# usb-sys.net
KiCad netlist of a schematic drawn in Altium Designer
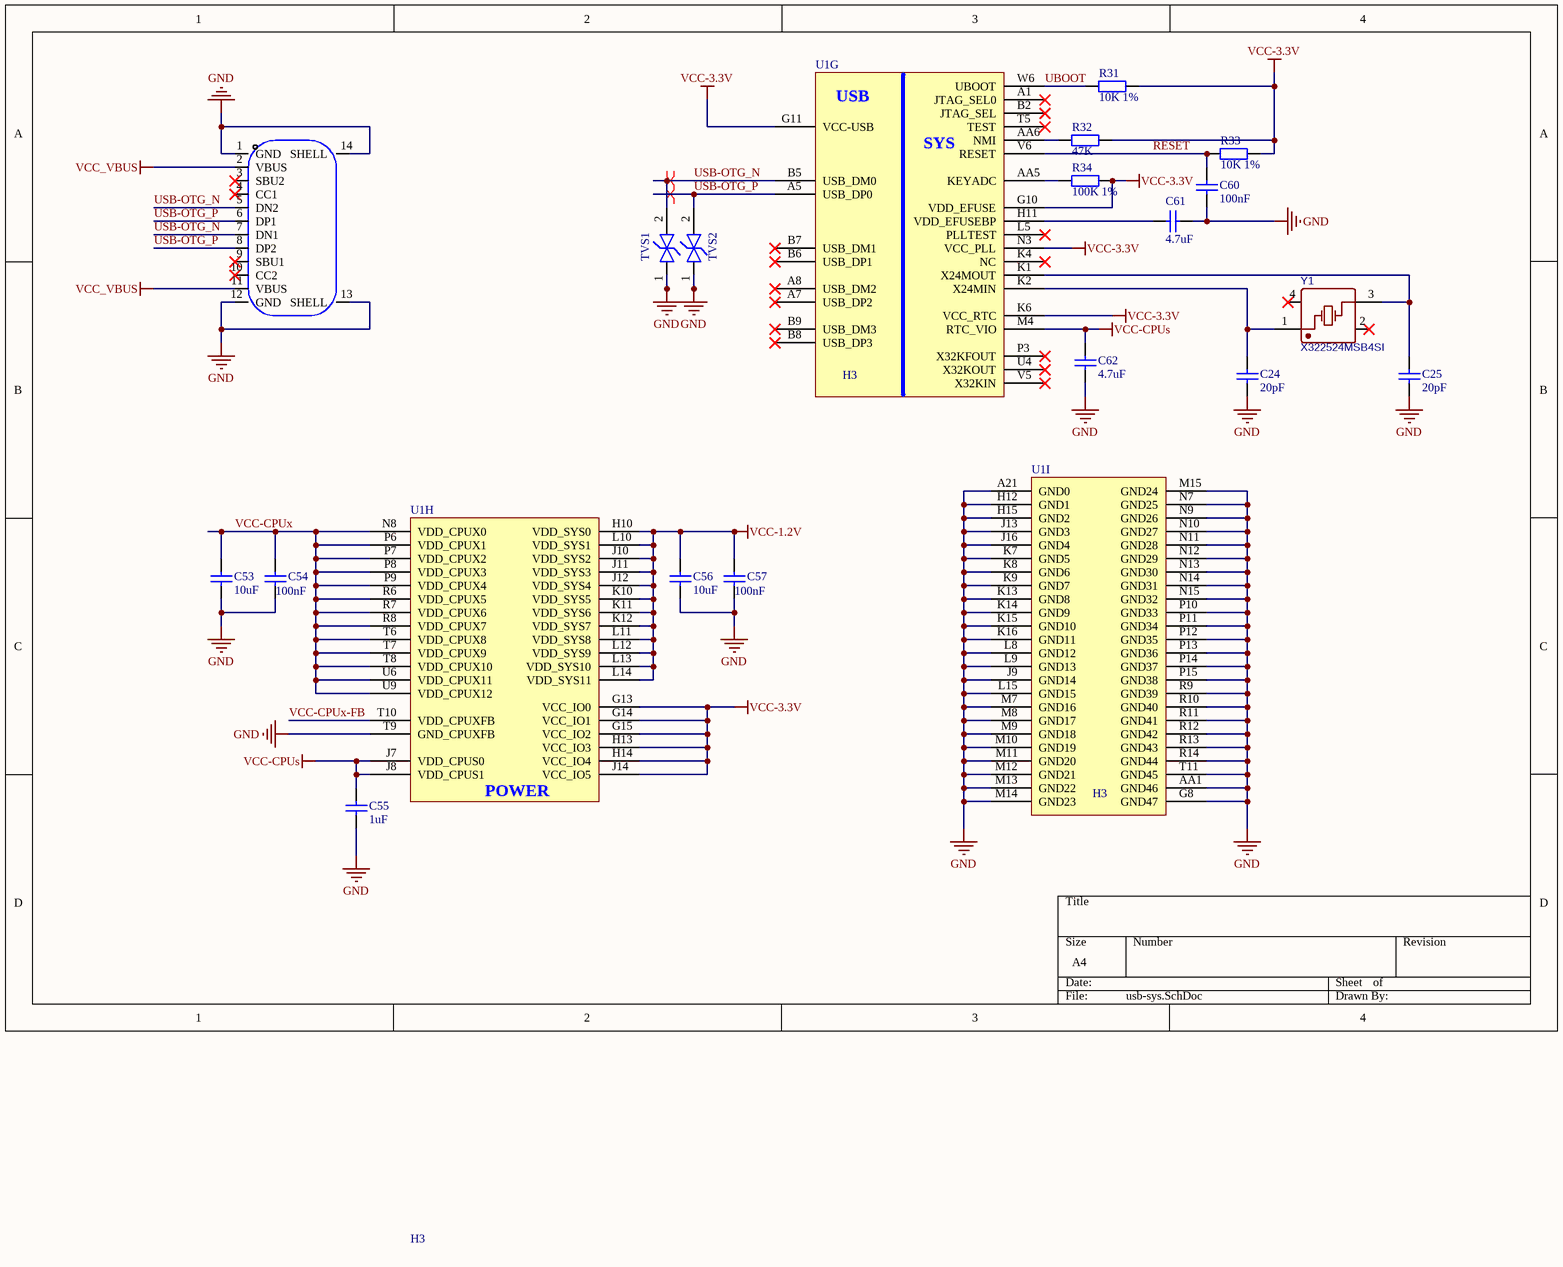
[diagram p0: usb-sys.SchDoc]

(export (version "E")
  (design (tool "Eeschema 10.0.6"))
  (components
    (comp (ref "C24")
      (value "20pF")
      (footprint "0402_C")
      (description "smd capacitor")
      (libsource (lib "Schlib") (part "CAP-SMD"))
    )
    (comp (ref "C25")
      (value "20pF")
      (footprint "0402_C")
      (description "smd capacitor")
      (libsource (lib "Schlib") (part "CAP-SMD"))
    )
    (comp (ref "C53")
      (value "10uF")
      (footprint "0402_C")
      (description "smd capacitor")
      (libsource (lib "Schlib") (part "CAP-SMD"))
    )
    (comp (ref "C54")
      (value "100nF")
      (footprint "0402_C")
      (description "smd capacitor")
      (libsource (lib "Schlib") (part "CAP-SMD"))
    )
    (comp (ref "C55")
      (value "1uF")
      (footprint "0402_C")
      (description "smd capacitor")
      (libsource (lib "Schlib") (part "CAP-SMD"))
    )
    (comp (ref "C56")
      (value "10uF")
      (footprint "0402_C")
      (description "smd capacitor")
      (libsource (lib "Schlib") (part "CAP-SMD"))
    )
    (comp (ref "C57")
      (value "100nF")
      (footprint "0402_C")
      (description "smd capacitor")
      (libsource (lib "Schlib") (part "CAP-SMD"))
    )
    (comp (ref "C60")
      (value "100nF")
      (footprint "0402_C")
      (description "smd capacitor")
      (libsource (lib "Schlib") (part "CAP-SMD"))
    )
    (comp (ref "C61")
      (value "4.7uF")
      (footprint "0402_C")
      (description "smd capacitor")
      (libsource (lib "Schlib") (part "CAP-SMD"))
    )
    (comp (ref "C62")
      (value "4.7uF")
      (footprint "0402_C")
      (description "smd capacitor")
      (libsource (lib "Schlib") (part "CAP-SMD"))
    )
    (comp (ref "R31")
      (value "10K 1%")
      (footprint "0402_R")
      (description "smd resistor")
      (libsource (lib "Schlib") (part "RES-SMD"))
    )
    (comp (ref "R32")
      (value "47K")
      (footprint "0402_R")
      (description "smd resistor")
      (libsource (lib "Schlib") (part "RES-SMD"))
    )
    (comp (ref "R33")
      (value "10K 1%")
      (footprint "0402_R")
      (description "smd resistor")
      (libsource (lib "Schlib") (part "RES-SMD"))
    )
    (comp (ref "R34")
      (value "100K 1%")
      (footprint "0402_R")
      (description "smd resistor")
      (libsource (lib "Schlib") (part "RES-SMD"))
    )
    (comp (ref "TVS1")
      (value "BSD5C051L")
      (footprint "SOD-523_TVS")
      (description "Transient Voltage Suppressor")
      (libsource (lib "Schlib") (part "TVS-DIODE-SMD"))
    )
    (comp (ref "TVS2")
      (value "BSD5C051L")
      (footprint "SOD-523_TVS")
      (description "Transient Voltage Suppressor")
      (libsource (lib "Schlib") (part "TVS-DIODE-SMD"))
    )
    (comp (ref "typec-1")
      (value "TYPE-C 16PIN 2MD(073)")
      (footprint "TYPE-C 16PIN 2MD(073)")
      (description "type-c")
      (libsource (lib "Schlib") (part "TYPE-C-16PIN"))
    )
    (comp (ref "U1")
      (value "H3")
      (footprint "allwinner-h3")
      (description "CPU")
      (libsource (lib "Schlib") (part "H3_CPU"))
    )
    (comp (ref "Y1")
      (value "X322524MSB4SI")
      (footprint "SMD3225-4P")
      (description "24mHZ ,20pf , no source smd crystal oscillator")
      (libsource (lib "Schlib") (part "XO-N-SOURCE-4pin"))
    )
  )
  (nets
    (net (code "1") (name "/RESET") (class "Default")
      (node (ref "C60") (pin "2") (pintype "passive"))
      (node (ref "R33") (pin "1") (pinfunction "1_1") (pintype "passive"))
      (node (ref "U1") (pin "V6") (pinfunction "RESET_V6") (pintype "passive"))
    )
    (net (code "2") (name "/UBOOT") (class "Default")
      (node (ref "R31") (pin "1") (pinfunction "1_1") (pintype "passive"))
      (node (ref "U1") (pin "W6") (pinfunction "UBOOT_W6") (pintype "passive"))
    )
    (net (code "3") (name "/USB-OTG_N") (class "Default")
      (node (ref "TVS1") (pin "2") (pinfunction "2_2") (pintype "passive"))
      (node (ref "U1") (pin "B5") (pinfunction "USB_DM0_B5") (pintype "passive"))
      (node (ref "typec-1") (pin "5") (pinfunction "DN2_5") (pintype "passive"))
      (node (ref "typec-1") (pin "7") (pinfunction "DN1_7") (pintype "passive"))
    )
    (net (code "4") (name "/USB-OTG_P") (class "Default")
      (node (ref "TVS2") (pin "2") (pinfunction "2_2") (pintype "passive"))
      (node (ref "U1") (pin "A5") (pinfunction "USB_DP0_A5") (pintype "passive"))
      (node (ref "typec-1") (pin "6") (pinfunction "DP1_6") (pintype "passive"))
      (node (ref "typec-1") (pin "8") (pinfunction "DP2_8") (pintype "passive"))
    )
    (net (code "5") (name "/VCC-CPUx") (class "Default")
      (node (ref "C53") (pin "1") (pintype "passive"))
      (node (ref "C54") (pin "1") (pintype "passive"))
      (node (ref "U1") (pin "N8") (pinfunction "VDD_CPUX0_N8") (pintype "passive"))
      (node (ref "U1") (pin "P6") (pinfunction "VDD_CPUX1_P6") (pintype "passive"))
      (node (ref "U1") (pin "P7") (pinfunction "VDD_CPUX2_P7") (pintype "passive"))
      (node (ref "U1") (pin "P8") (pinfunction "VDD_CPUX3_P8") (pintype "passive"))
      (node (ref "U1") (pin "P9") (pinfunction "VDD_CPUX4_P9") (pintype "passive"))
      (node (ref "U1") (pin "R6") (pinfunction "VDD_CPUX5_R6") (pintype "passive"))
      (node (ref "U1") (pin "R7") (pinfunction "VDD_CPUX6_R7") (pintype "passive"))
      (node (ref "U1") (pin "R8") (pinfunction "VDD_CPUX7_R8") (pintype "passive"))
      (node (ref "U1") (pin "T6") (pinfunction "VDD_CPUX8_T6") (pintype "passive"))
      (node (ref "U1") (pin "T7") (pinfunction "VDD_CPUX9_T7") (pintype "passive"))
      (node (ref "U1") (pin "T8") (pinfunction "VDD_CPUX10_T8") (pintype "passive"))
      (node (ref "U1") (pin "U6") (pinfunction "VDD_CPUX11_U6") (pintype "passive"))
      (node (ref "U1") (pin "U9") (pinfunction "VDD_CPUX12_U9") (pintype "passive"))
    )
    (net (code "6") (name "/VCC-CPUx-FB") (class "Default")
      (node (ref "U1") (pin "T10") (pinfunction "VDD_CPUXFB_T10") (pintype "passive"))
    )
    (net (code "7") (name "GND") (class "Default")
      (node (ref "C24") (pin "2") (pintype "passive"))
      (node (ref "C25") (pin "2") (pintype "passive"))
      (node (ref "C53") (pin "2") (pintype "passive"))
      (node (ref "C54") (pin "2") (pintype "passive"))
      (node (ref "C55") (pin "2") (pintype "passive"))
      (node (ref "C56") (pin "2") (pintype "passive"))
      (node (ref "C57") (pin "2") (pintype "passive"))
      (node (ref "C60") (pin "1") (pintype "passive"))
      (node (ref "C61") (pin "2") (pintype "passive"))
      (node (ref "C62") (pin "2") (pintype "passive"))
      (node (ref "TVS1") (pin "1") (pinfunction "1_1") (pintype "passive"))
      (node (ref "TVS2") (pin "1") (pinfunction "1_1") (pintype "passive"))
      (node (ref "U1") (pin "A21") (pinfunction "GND0_A21") (pintype "passive"))
      (node (ref "U1") (pin "AA1") (pinfunction "GND46_AA1") (pintype "passive"))
      (node (ref "U1") (pin "G8") (pinfunction "GND47_G8") (pintype "passive"))
      (node (ref "U1") (pin "H12") (pinfunction "GND1_H12") (pintype "passive"))
      (node (ref "U1") (pin "H15") (pinfunction "GND2_H15") (pintype "passive"))
      (node (ref "U1") (pin "J13") (pinfunction "GND3_J13") (pintype "passive"))
      (node (ref "U1") (pin "J16") (pinfunction "GND4_J16") (pintype "passive"))
      (node (ref "U1") (pin "J9") (pinfunction "GND14_J9") (pintype "passive"))
      (node (ref "U1") (pin "K13") (pinfunction "GND8_K13") (pintype "passive"))
      (node (ref "U1") (pin "K14") (pinfunction "GND9_K14") (pintype "passive"))
      (node (ref "U1") (pin "K15") (pinfunction "GND10_K15") (pintype "passive"))
      (node (ref "U1") (pin "K16") (pinfunction "GND11_K16") (pintype "passive"))
      (node (ref "U1") (pin "K7") (pinfunction "GND5_K7") (pintype "passive"))
      (node (ref "U1") (pin "K8") (pinfunction "GND6_K8") (pintype "passive"))
      (node (ref "U1") (pin "K9") (pinfunction "GND7_K9") (pintype "passive"))
      (node (ref "U1") (pin "L15") (pinfunction "GND15_L15") (pintype "passive"))
      (node (ref "U1") (pin "L8") (pinfunction "GND12_L8") (pintype "passive"))
      (node (ref "U1") (pin "L9") (pinfunction "GND13_L9") (pintype "passive"))
      (node (ref "U1") (pin "M10") (pinfunction "GND19_M10") (pintype "passive"))
      (node (ref "U1") (pin "M11") (pinfunction "GND20_M11") (pintype "passive"))
      (node (ref "U1") (pin "M12") (pinfunction "GND21_M12") (pintype "passive"))
      (node (ref "U1") (pin "M13") (pinfunction "GND22_M13") (pintype "passive"))
      (node (ref "U1") (pin "M14") (pinfunction "GND23_M14") (pintype "passive"))
      (node (ref "U1") (pin "M15") (pinfunction "GND24_M15") (pintype "passive"))
      (node (ref "U1") (pin "M7") (pinfunction "GND16_M7") (pintype "passive"))
      (node (ref "U1") (pin "M8") (pinfunction "GND17_M8") (pintype "passive"))
      (node (ref "U1") (pin "M9") (pinfunction "GND18_M9") (pintype "passive"))
      (node (ref "U1") (pin "N10") (pinfunction "GND27_N10") (pintype "passive"))
      (node (ref "U1") (pin "N11") (pinfunction "GND28_N11") (pintype "passive"))
      (node (ref "U1") (pin "N12") (pinfunction "GND29_N12") (pintype "passive"))
      (node (ref "U1") (pin "N13") (pinfunction "GND30_N13") (pintype "passive"))
      (node (ref "U1") (pin "N14") (pinfunction "GND31_N14") (pintype "passive"))
      (node (ref "U1") (pin "N15") (pinfunction "GND32_N15") (pintype "passive"))
      (node (ref "U1") (pin "N7") (pinfunction "GND25_N7") (pintype "passive"))
      (node (ref "U1") (pin "N9") (pinfunction "GND26_N9") (pintype "passive"))
      (node (ref "U1") (pin "P10") (pinfunction "GND33_P10") (pintype "passive"))
      (node (ref "U1") (pin "P11") (pinfunction "GND34_P11") (pintype "passive"))
      (node (ref "U1") (pin "P12") (pinfunction "GND35_P12") (pintype "passive"))
      (node (ref "U1") (pin "P13") (pinfunction "GND36_P13") (pintype "passive"))
      (node (ref "U1") (pin "P14") (pinfunction "GND37_P14") (pintype "passive"))
      (node (ref "U1") (pin "P15") (pinfunction "GND38_P15") (pintype "passive"))
      (node (ref "U1") (pin "R10") (pinfunction "GND40_R10") (pintype "passive"))
      (node (ref "U1") (pin "R11") (pinfunction "GND41_R11") (pintype "passive"))
      (node (ref "U1") (pin "R12") (pinfunction "GND42_R12") (pintype "passive"))
      (node (ref "U1") (pin "R13") (pinfunction "GND43_R13") (pintype "passive"))
      (node (ref "U1") (pin "R14") (pinfunction "GND44_R14") (pintype "passive"))
      (node (ref "U1") (pin "R9") (pinfunction "GND39_R9") (pintype "passive"))
      (node (ref "U1") (pin "T11") (pinfunction "GND45_T11") (pintype "passive"))
      (node (ref "U1") (pin "T9") (pinfunction "GND_CPUXFB_T9") (pintype "passive"))
      (node (ref "typec-1") (pin "1") (pinfunction "GND_1") (pintype "passive"))
      (node (ref "typec-1") (pin "12") (pinfunction "GND_12") (pintype "passive"))
      (node (ref "typec-1") (pin "13") (pinfunction "SHELL_13") (pintype "passive"))
      (node (ref "typec-1") (pin "14") (pinfunction "SHELL_14") (pintype "passive"))
    )
    (net (code "8") (name "Net-(U1G-KEYADC)") (class "Default")
      (node (ref "R34") (pin "1") (pinfunction "1_1") (pintype "passive"))
      (node (ref "U1") (pin "AA5") (pinfunction "KEYADC_AA5") (pintype "passive"))
    )
    (net (code "9") (name "Net-(U1G-NMI)") (class "Default")
      (node (ref "R32") (pin "1") (pinfunction "1_1") (pintype "passive"))
      (node (ref "U1") (pin "AA6") (pinfunction "NMI_AA6") (pintype "passive"))
    )
    (net (code "10") (name "Net-(U1G-VDD_EFUSEBP)") (class "Default")
      (node (ref "C61") (pin "1") (pintype "passive"))
      (node (ref "U1") (pin "H11") (pinfunction "VDD_EFUSEBP_H11") (pintype "passive"))
    )
    (net (code "11") (name "Net-(U1G-X24MIN)") (class "Default")
      (node (ref "C24") (pin "1") (pintype "passive"))
      (node (ref "U1") (pin "K2") (pinfunction "X24MIN_K2") (pintype "passive"))
      (node (ref "Y1") (pin "1") (pinfunction "OE#_1") (pintype "passive"))
    )
    (net (code "12") (name "Net-(U1G-X24MOUT)") (class "Default")
      (node (ref "C25") (pin "1") (pintype "passive"))
      (node (ref "U1") (pin "K1") (pinfunction "X24MOUT_K1") (pintype "passive"))
      (node (ref "Y1") (pin "3") (pinfunction "OUT_3") (pintype "passive"))
    )
    (net (code "13") (name "VCC-1.2V") (class "Default")
      (node (ref "C56") (pin "1") (pintype "passive"))
      (node (ref "C57") (pin "1") (pintype "passive"))
      (node (ref "U1") (pin "H10") (pinfunction "VDD_SYS0_H10") (pintype "passive"))
      (node (ref "U1") (pin "J10") (pinfunction "VDD_SYS2_J10") (pintype "passive"))
      (node (ref "U1") (pin "J11") (pinfunction "VDD_SYS3_J11") (pintype "passive"))
      (node (ref "U1") (pin "J12") (pinfunction "VDD_SYS4_J12") (pintype "passive"))
      (node (ref "U1") (pin "K10") (pinfunction "VDD_SYS5_K10") (pintype "passive"))
      (node (ref "U1") (pin "K11") (pinfunction "VDD_SYS6_K11") (pintype "passive"))
      (node (ref "U1") (pin "K12") (pinfunction "VDD_SYS7_K12") (pintype "passive"))
      (node (ref "U1") (pin "L10") (pinfunction "VDD_SYS1_L10") (pintype "passive"))
      (node (ref "U1") (pin "L11") (pinfunction "VDD_SYS8_L11") (pintype "passive"))
      (node (ref "U1") (pin "L12") (pinfunction "VDD_SYS9_L12") (pintype "passive"))
      (node (ref "U1") (pin "L13") (pinfunction "VDD_SYS10_L13") (pintype "passive"))
      (node (ref "U1") (pin "L14") (pinfunction "VDD_SYS11_L14") (pintype "passive"))
    )
    (net (code "14") (name "VCC-3.3V") (class "Default")
      (node (ref "R31") (pin "2") (pinfunction "2_2") (pintype "passive"))
      (node (ref "R32") (pin "2") (pinfunction "2_2") (pintype "passive"))
      (node (ref "R33") (pin "2") (pinfunction "2_2") (pintype "passive"))
      (node (ref "R34") (pin "2") (pinfunction "2_2") (pintype "passive"))
      (node (ref "U1") (pin "G10") (pinfunction "VDD_EFUSE_G10") (pintype "passive"))
      (node (ref "U1") (pin "G11") (pinfunction "VCC-USB_G11") (pintype "passive"))
      (node (ref "U1") (pin "G13") (pinfunction "VCC_IO0_G13") (pintype "passive"))
      (node (ref "U1") (pin "G14") (pinfunction "VCC_IO1_G14") (pintype "passive"))
      (node (ref "U1") (pin "G15") (pinfunction "VCC_IO2_G15") (pintype "passive"))
      (node (ref "U1") (pin "H13") (pinfunction "VCC_IO3_H13") (pintype "passive"))
      (node (ref "U1") (pin "H14") (pinfunction "VCC_IO4_H14") (pintype "passive"))
      (node (ref "U1") (pin "J14") (pinfunction "VCC_IO5_J14") (pintype "passive"))
      (node (ref "U1") (pin "K6") (pinfunction "VCC_RTC_K6") (pintype "passive"))
      (node (ref "U1") (pin "N3") (pinfunction "VCC_PLL_N3") (pintype "passive"))
    )
    (net (code "15") (name "VCC-CPUs") (class "Default")
      (node (ref "C55") (pin "1") (pintype "passive"))
      (node (ref "C62") (pin "1") (pintype "passive"))
      (node (ref "U1") (pin "J7") (pinfunction "VDD_CPUS0_J7") (pintype "passive"))
      (node (ref "U1") (pin "J8") (pinfunction "VDD_CPUS1_J8") (pintype "passive"))
      (node (ref "U1") (pin "M4") (pinfunction "RTC_VIO_M4") (pintype "passive"))
    )
    (net (code "16") (name "VCC_VBUS") (class "Default")
      (node (ref "typec-1") (pin "11") (pinfunction "VBUS_11") (pintype "passive"))
      (node (ref "typec-1") (pin "2") (pinfunction "VBUS_2") (pintype "passive"))
    )
    (net (code "17") (name "unconnected-(U1G-JTAG_SEL-PadB2)") (class "Default")
      (node (ref "U1") (pin "B2") (pinfunction "JTAG_SEL_B2") (pintype "passive+no_connect"))
    )
    (net (code "18") (name "unconnected-(U1G-JTAG_SEL0-PadA1)") (class "Default")
      (node (ref "U1") (pin "A1") (pinfunction "JTAG_SEL0_A1") (pintype "passive+no_connect"))
    )
    (net (code "19") (name "unconnected-(U1G-NC-PadK4)") (class "Default")
      (node (ref "U1") (pin "K4") (pinfunction "NC_K4") (pintype "passive+no_connect"))
    )
    (net (code "20") (name "unconnected-(U1G-PLLTEST-PadL5)") (class "Default")
      (node (ref "U1") (pin "L5") (pinfunction "PLLTEST_L5") (pintype "passive+no_connect"))
    )
    (net (code "21") (name "unconnected-(U1G-TEST-PadT5)") (class "Default")
      (node (ref "U1") (pin "T5") (pinfunction "TEST_T5") (pintype "passive+no_connect"))
    )
    (net (code "22") (name "unconnected-(U1G-USB_DM1-PadB7)") (class "Default")
      (node (ref "U1") (pin "B7") (pinfunction "USB_DM1_B7") (pintype "passive+no_connect"))
    )
    (net (code "23") (name "unconnected-(U1G-USB_DM2-PadA8)") (class "Default")
      (node (ref "U1") (pin "A8") (pinfunction "USB_DM2_A8") (pintype "passive+no_connect"))
    )
    (net (code "24") (name "unconnected-(U1G-USB_DM3-PadB9)") (class "Default")
      (node (ref "U1") (pin "B9") (pinfunction "USB_DM3_B9") (pintype "passive+no_connect"))
    )
    (net (code "25") (name "unconnected-(U1G-USB_DP1-PadB6)") (class "Default")
      (node (ref "U1") (pin "B6") (pinfunction "USB_DP1_B6") (pintype "passive+no_connect"))
    )
    (net (code "26") (name "unconnected-(U1G-USB_DP2-PadA7)") (class "Default")
      (node (ref "U1") (pin "A7") (pinfunction "USB_DP2_A7") (pintype "passive+no_connect"))
    )
    (net (code "27") (name "unconnected-(U1G-USB_DP3-PadB8)") (class "Default")
      (node (ref "U1") (pin "B8") (pinfunction "USB_DP3_B8") (pintype "passive+no_connect"))
    )
    (net (code "28") (name "unconnected-(U1G-X32KFOUT-PadP3)") (class "Default")
      (node (ref "U1") (pin "P3") (pinfunction "X32KFOUT_P3") (pintype "passive+no_connect"))
    )
    (net (code "29") (name "unconnected-(U1G-X32KIN-PadV5)") (class "Default")
      (node (ref "U1") (pin "V5") (pinfunction "X32KIN_V5") (pintype "passive+no_connect"))
    )
    (net (code "30") (name "unconnected-(U1G-X32KOUT-PadU4)") (class "Default")
      (node (ref "U1") (pin "U4") (pinfunction "X32KOUT_U4") (pintype "passive+no_connect"))
    )
    (net (code "31") (name "unconnected-(Y1-GND-Pad2)") (class "Default")
      (node (ref "Y1") (pin "2") (pinfunction "GND_2") (pintype "passive+no_connect"))
    )
    (net (code "32") (name "unconnected-(Y1-VDD-Pad4)") (class "Default")
      (node (ref "Y1") (pin "4") (pinfunction "VDD_4") (pintype "passive+no_connect"))
    )
    (net (code "33") (name "unconnected-(typec-1-CC1-Pad4)") (class "Default")
      (node (ref "typec-1") (pin "4") (pinfunction "CC1_4") (pintype "passive+no_connect"))
    )
    (net (code "34") (name "unconnected-(typec-1-CC2-Pad10)") (class "Default")
      (node (ref "typec-1") (pin "10") (pinfunction "CC2_10") (pintype "passive+no_connect"))
    )
    (net (code "35") (name "unconnected-(typec-1-SBU1-Pad9)") (class "Default")
      (node (ref "typec-1") (pin "9") (pinfunction "SBU1_9") (pintype "passive+no_connect"))
    )
    (net (code "36") (name "unconnected-(typec-1-SBU2-Pad3)") (class "Default")
      (node (ref "typec-1") (pin "3") (pinfunction "SBU2_3") (pintype "passive+no_connect"))
    )
  )
)
